# P03_Connectors.net
KiCad netlist of a schematic drawn in Altium Designer
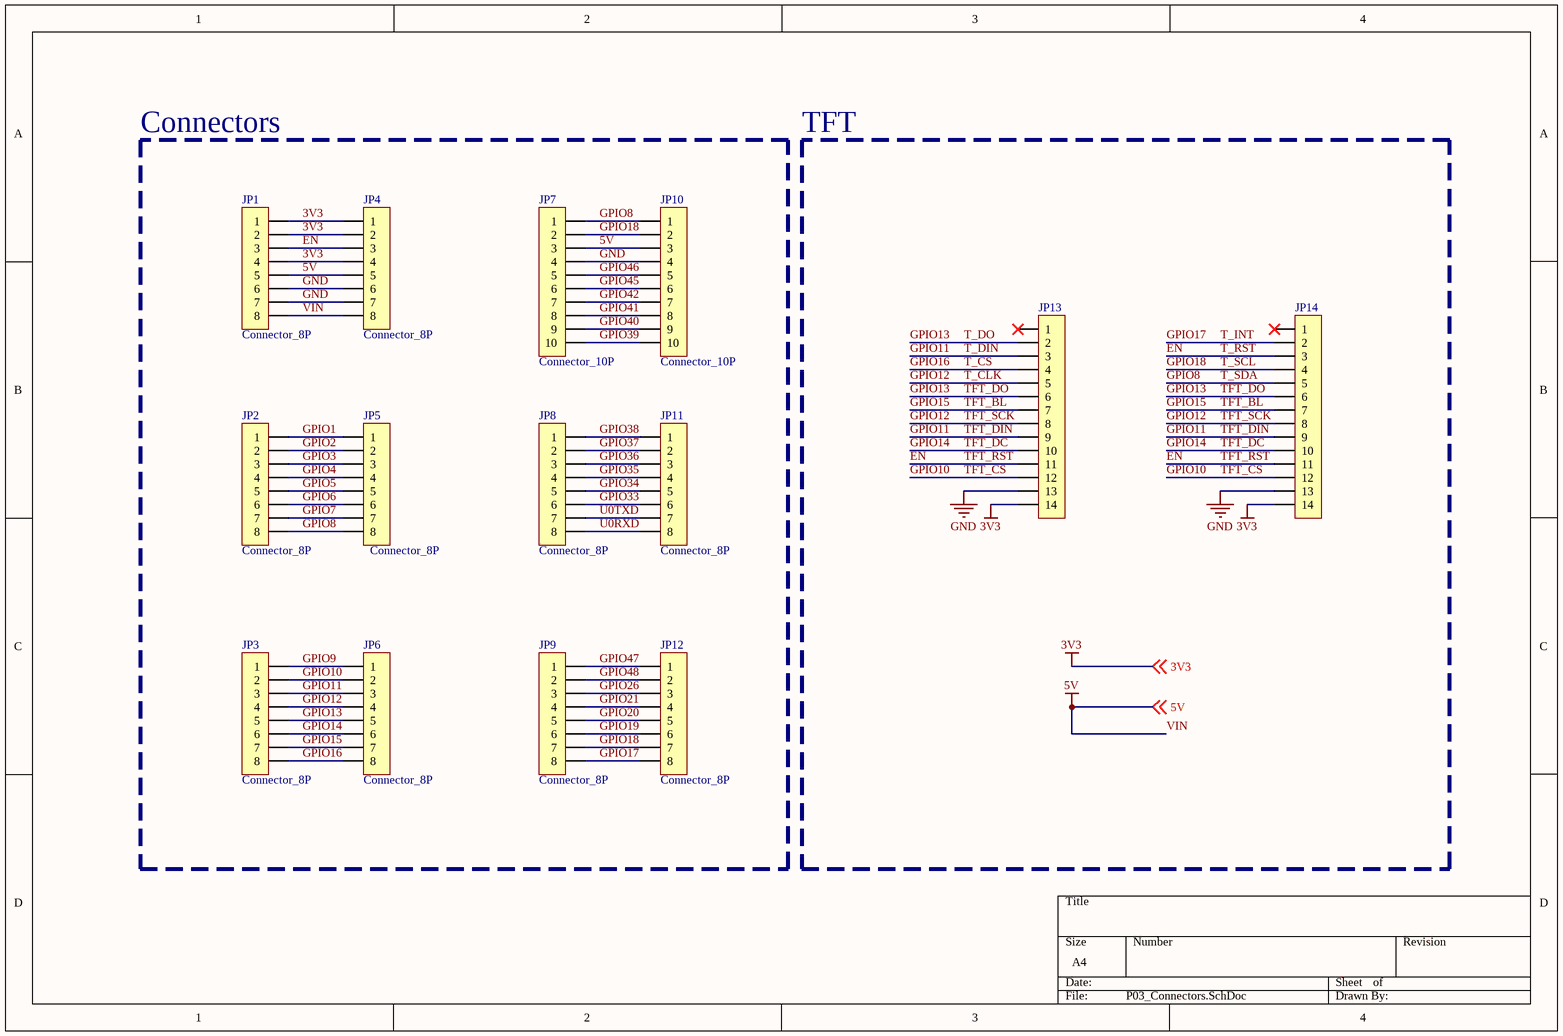
[diagram p0: P03_Connectors.SchDoc]

(export (version "E")
  (design (tool "Eeschema 10.0.6"))
  (components
    (comp (ref "JP1")
      (value "Connector_8P")
      (footprint "排母_2.54mm_8P")
      (libsource (lib "Schlib") (part "Connector_8P"))
    )
    (comp (ref "JP2")
      (value "Connector_8P")
      (footprint "排母_2.54mm_8P")
      (libsource (lib "Schlib") (part "Connector_8P"))
    )
    (comp (ref "JP3")
      (value "Connector_8P")
      (footprint "排母_2.54mm_8P")
      (libsource (lib "Schlib") (part "Connector_8P"))
    )
    (comp (ref "JP4")
      (value "Connector_8P")
      (footprint "排针_2.54mm_8P")
      (libsource (lib "") (part "Connector_8P_1"))
    )
    (comp (ref "JP5")
      (value "Connector_8P")
      (footprint "排针_2.54mm_8P")
      (libsource (lib "") (part "Connector_8P_1"))
    )
    (comp (ref "JP6")
      (value "Connector_8P")
      (footprint "排针_2.54mm_8P")
      (libsource (lib "") (part "Connector_8P_1"))
    )
    (comp (ref "JP7")
      (value "Connector_10P")
      (footprint "排母_2.54mm_10P")
      (libsource (lib "") (part "Connector_10P_1"))
    )
    (comp (ref "JP8")
      (value "Connector_8P")
      (footprint "排母_2.54mm_8P")
      (libsource (lib "Schlib") (part "Connector_8P"))
    )
    (comp (ref "JP9")
      (value "Connector_8P")
      (footprint "排母_2.54mm_8P")
      (libsource (lib "Schlib") (part "Connector_8P"))
    )
    (comp (ref "JP10")
      (value "Connector_10P")
      (footprint "排针_2.54mm_10P")
      (libsource (lib "Schlib") (part "Connector_10P"))
    )
    (comp (ref "JP11")
      (value "Connector_8P")
      (footprint "排针_2.54mm_8P")
      (libsource (lib "") (part "Connector_8P_1"))
    )
    (comp (ref "JP12")
      (value "Connector_8P")
      (footprint "排针_2.54mm_8P")
      (libsource (lib "") (part "Connector_8P_1"))
    )
    (comp (ref "JP13")
      (value "HDR-1X14")
      (footprint "HDR2.54-M-LI-14P")
      (description "14P接插件")
      (libsource (lib "5.5 - 2.54mm(100mil)连接器(XH2.54)") (part "Header 14"))
    )
    (comp (ref "JP14")
      (value "HDR-1X14")
      (footprint "HDR2.54-M-LI-14P")
      (description "14P接插件")
      (libsource (lib "5.5 - 2.54mm(100mil)连接器(XH2.54)") (part "Header 14"))
    )
  )
  (nets
    (net (code "1") (name "/EN") (class "Default")
      (node (ref "JP1") (pin "3") (pinfunction "3_3") (pintype "passive"))
      (node (ref "JP13") (pin "11") (pinfunction "11_11") (pintype "passive"))
      (node (ref "JP14") (pin "11") (pinfunction "11_11") (pintype "passive"))
      (node (ref "JP14") (pin "3") (pinfunction "3_3") (pintype "passive"))
      (node (ref "JP4") (pin "3") (pinfunction "3_3") (pintype "passive"))
    )
    (net (code "2") (name "/GPIO1") (class "Default")
      (node (ref "JP2") (pin "1") (pinfunction "1_1") (pintype "passive"))
      (node (ref "JP5") (pin "1") (pinfunction "1_1") (pintype "passive"))
    )
    (net (code "3") (name "/GPIO2") (class "Default")
      (node (ref "JP2") (pin "2") (pinfunction "2_2") (pintype "passive"))
      (node (ref "JP5") (pin "2") (pinfunction "2_2") (pintype "passive"))
    )
    (net (code "4") (name "/GPIO3") (class "Default")
      (node (ref "JP2") (pin "3") (pinfunction "3_3") (pintype "passive"))
      (node (ref "JP5") (pin "3") (pinfunction "3_3") (pintype "passive"))
    )
    (net (code "5") (name "/GPIO4") (class "Default")
      (node (ref "JP2") (pin "4") (pinfunction "4_4") (pintype "passive"))
      (node (ref "JP5") (pin "4") (pinfunction "4_4") (pintype "passive"))
    )
    (net (code "6") (name "/GPIO5") (class "Default")
      (node (ref "JP2") (pin "5") (pinfunction "5_5") (pintype "passive"))
      (node (ref "JP5") (pin "5") (pinfunction "5_5") (pintype "passive"))
    )
    (net (code "7") (name "/GPIO6") (class "Default")
      (node (ref "JP2") (pin "6") (pinfunction "6_6") (pintype "passive"))
      (node (ref "JP5") (pin "6") (pinfunction "6_6") (pintype "passive"))
    )
    (net (code "8") (name "/GPIO7") (class "Default")
      (node (ref "JP2") (pin "7") (pinfunction "7_7") (pintype "passive"))
      (node (ref "JP5") (pin "7") (pinfunction "7_7") (pintype "passive"))
    )
    (net (code "9") (name "/GPIO8") (class "Default")
      (node (ref "JP10") (pin "1") (pinfunction "1_1") (pintype "passive"))
      (node (ref "JP14") (pin "5") (pinfunction "5_5") (pintype "passive"))
      (node (ref "JP2") (pin "8") (pinfunction "8_8") (pintype "passive"))
      (node (ref "JP5") (pin "8") (pinfunction "8_8") (pintype "passive"))
      (node (ref "JP7") (pin "1") (pinfunction "1_1") (pintype "passive"))
    )
    (net (code "10") (name "/GPIO9") (class "Default")
      (node (ref "JP3") (pin "1") (pinfunction "1_1") (pintype "passive"))
      (node (ref "JP6") (pin "1") (pinfunction "1_1") (pintype "passive"))
    )
    (net (code "11") (name "/GPIO10") (class "Default")
      (node (ref "JP13") (pin "12") (pinfunction "12_12") (pintype "passive"))
      (node (ref "JP14") (pin "12") (pinfunction "12_12") (pintype "passive"))
      (node (ref "JP3") (pin "2") (pinfunction "2_2") (pintype "passive"))
      (node (ref "JP6") (pin "2") (pinfunction "2_2") (pintype "passive"))
    )
    (net (code "12") (name "/GPIO11") (class "Default")
      (node (ref "JP13") (pin "3") (pinfunction "3_3") (pintype "passive"))
      (node (ref "JP13") (pin "9") (pinfunction "9_9") (pintype "passive"))
      (node (ref "JP14") (pin "9") (pinfunction "9_9") (pintype "passive"))
      (node (ref "JP3") (pin "3") (pinfunction "3_3") (pintype "passive"))
      (node (ref "JP6") (pin "3") (pinfunction "3_3") (pintype "passive"))
    )
    (net (code "13") (name "/GPIO12") (class "Default")
      (node (ref "JP13") (pin "5") (pinfunction "5_5") (pintype "passive"))
      (node (ref "JP13") (pin "8") (pinfunction "8_8") (pintype "passive"))
      (node (ref "JP14") (pin "8") (pinfunction "8_8") (pintype "passive"))
      (node (ref "JP3") (pin "4") (pinfunction "4_4") (pintype "passive"))
      (node (ref "JP6") (pin "4") (pinfunction "4_4") (pintype "passive"))
    )
    (net (code "14") (name "/GPIO13") (class "Default")
      (node (ref "JP13") (pin "2") (pinfunction "2_2") (pintype "passive"))
      (node (ref "JP13") (pin "6") (pinfunction "6_6") (pintype "passive"))
      (node (ref "JP14") (pin "6") (pinfunction "6_6") (pintype "passive"))
      (node (ref "JP3") (pin "5") (pinfunction "5_5") (pintype "passive"))
      (node (ref "JP6") (pin "5") (pinfunction "5_5") (pintype "passive"))
    )
    (net (code "15") (name "/GPIO14") (class "Default")
      (node (ref "JP13") (pin "10") (pinfunction "10_10") (pintype "passive"))
      (node (ref "JP14") (pin "10") (pinfunction "10_10") (pintype "passive"))
      (node (ref "JP3") (pin "6") (pinfunction "6_6") (pintype "passive"))
      (node (ref "JP6") (pin "6") (pinfunction "6_6") (pintype "passive"))
    )
    (net (code "16") (name "/GPIO15") (class "Default")
      (node (ref "JP13") (pin "7") (pinfunction "7_7") (pintype "passive"))
      (node (ref "JP14") (pin "7") (pinfunction "7_7") (pintype "passive"))
      (node (ref "JP3") (pin "7") (pinfunction "7_7") (pintype "passive"))
      (node (ref "JP6") (pin "7") (pinfunction "7_7") (pintype "passive"))
    )
    (net (code "17") (name "/GPIO16") (class "Default")
      (node (ref "JP13") (pin "4") (pinfunction "4_4") (pintype "passive"))
      (node (ref "JP3") (pin "8") (pinfunction "8_8") (pintype "passive"))
      (node (ref "JP6") (pin "8") (pinfunction "8_8") (pintype "passive"))
    )
    (net (code "18") (name "/GPIO17") (class "Default")
      (node (ref "JP12") (pin "8") (pinfunction "8_8") (pintype "passive"))
      (node (ref "JP14") (pin "2") (pinfunction "2_2") (pintype "passive"))
      (node (ref "JP9") (pin "8") (pinfunction "8_8") (pintype "passive"))
    )
    (net (code "19") (name "/GPIO18") (class "Default")
      (node (ref "JP10") (pin "2") (pinfunction "2_2") (pintype "passive"))
      (node (ref "JP12") (pin "7") (pinfunction "7_7") (pintype "passive"))
      (node (ref "JP14") (pin "4") (pinfunction "4_4") (pintype "passive"))
      (node (ref "JP7") (pin "2") (pinfunction "2_2") (pintype "passive"))
      (node (ref "JP9") (pin "7") (pinfunction "7_7") (pintype "passive"))
    )
    (net (code "20") (name "/GPIO19") (class "Default")
      (node (ref "JP12") (pin "6") (pinfunction "6_6") (pintype "passive"))
      (node (ref "JP9") (pin "6") (pinfunction "6_6") (pintype "passive"))
    )
    (net (code "21") (name "/GPIO20") (class "Default")
      (node (ref "JP12") (pin "5") (pinfunction "5_5") (pintype "passive"))
      (node (ref "JP9") (pin "5") (pinfunction "5_5") (pintype "passive"))
    )
    (net (code "22") (name "/GPIO21") (class "Default")
      (node (ref "JP12") (pin "4") (pinfunction "4_4") (pintype "passive"))
      (node (ref "JP9") (pin "4") (pinfunction "4_4") (pintype "passive"))
    )
    (net (code "23") (name "/GPIO26") (class "Default")
      (node (ref "JP12") (pin "3") (pinfunction "3_3") (pintype "passive"))
      (node (ref "JP9") (pin "3") (pinfunction "3_3") (pintype "passive"))
    )
    (net (code "24") (name "/GPIO33") (class "Default")
      (node (ref "JP11") (pin "6") (pinfunction "6_6") (pintype "passive"))
      (node (ref "JP8") (pin "6") (pinfunction "6_6") (pintype "passive"))
    )
    (net (code "25") (name "/GPIO34") (class "Default")
      (node (ref "JP11") (pin "5") (pinfunction "5_5") (pintype "passive"))
      (node (ref "JP8") (pin "5") (pinfunction "5_5") (pintype "passive"))
    )
    (net (code "26") (name "/GPIO35") (class "Default")
      (node (ref "JP11") (pin "4") (pinfunction "4_4") (pintype "passive"))
      (node (ref "JP8") (pin "4") (pinfunction "4_4") (pintype "passive"))
    )
    (net (code "27") (name "/GPIO36") (class "Default")
      (node (ref "JP11") (pin "3") (pinfunction "3_3") (pintype "passive"))
      (node (ref "JP8") (pin "3") (pinfunction "3_3") (pintype "passive"))
    )
    (net (code "28") (name "/GPIO37") (class "Default")
      (node (ref "JP11") (pin "2") (pinfunction "2_2") (pintype "passive"))
      (node (ref "JP8") (pin "2") (pinfunction "2_2") (pintype "passive"))
    )
    (net (code "29") (name "/GPIO38") (class "Default")
      (node (ref "JP11") (pin "1") (pinfunction "1_1") (pintype "passive"))
      (node (ref "JP8") (pin "1") (pinfunction "1_1") (pintype "passive"))
    )
    (net (code "30") (name "/GPIO39") (class "Default")
      (node (ref "JP10") (pin "10") (pinfunction "10_10") (pintype "passive"))
      (node (ref "JP7") (pin "10") (pinfunction "10_10") (pintype "passive"))
    )
    (net (code "31") (name "/GPIO40") (class "Default")
      (node (ref "JP10") (pin "9") (pinfunction "9_9") (pintype "passive"))
      (node (ref "JP7") (pin "9") (pinfunction "9_9") (pintype "passive"))
    )
    (net (code "32") (name "/GPIO41") (class "Default")
      (node (ref "JP10") (pin "8") (pinfunction "8_8") (pintype "passive"))
      (node (ref "JP7") (pin "8") (pinfunction "8_8") (pintype "passive"))
    )
    (net (code "33") (name "/GPIO42") (class "Default")
      (node (ref "JP10") (pin "7") (pinfunction "7_7") (pintype "passive"))
      (node (ref "JP7") (pin "7") (pinfunction "7_7") (pintype "passive"))
    )
    (net (code "34") (name "/GPIO45") (class "Default")
      (node (ref "JP10") (pin "6") (pinfunction "6_6") (pintype "passive"))
      (node (ref "JP7") (pin "6") (pinfunction "6_6") (pintype "passive"))
    )
    (net (code "35") (name "/GPIO46") (class "Default")
      (node (ref "JP10") (pin "5") (pinfunction "5_5") (pintype "passive"))
      (node (ref "JP7") (pin "5") (pinfunction "5_5") (pintype "passive"))
    )
    (net (code "36") (name "/GPIO47") (class "Default")
      (node (ref "JP12") (pin "1") (pinfunction "1_1") (pintype "passive"))
      (node (ref "JP9") (pin "1") (pinfunction "1_1") (pintype "passive"))
    )
    (net (code "37") (name "/GPIO48") (class "Default")
      (node (ref "JP12") (pin "2") (pinfunction "2_2") (pintype "passive"))
      (node (ref "JP9") (pin "2") (pinfunction "2_2") (pintype "passive"))
    )
    (net (code "38") (name "/U0RXD") (class "Default")
      (node (ref "JP11") (pin "8") (pinfunction "8_8") (pintype "passive"))
      (node (ref "JP8") (pin "8") (pinfunction "8_8") (pintype "passive"))
    )
    (net (code "39") (name "/U0TXD") (class "Default")
      (node (ref "JP11") (pin "7") (pinfunction "7_7") (pintype "passive"))
      (node (ref "JP8") (pin "7") (pinfunction "7_7") (pintype "passive"))
    )
    (net (code "40") (name "3V3") (class "Default")
      (node (ref "JP1") (pin "1") (pinfunction "1_1") (pintype "passive"))
      (node (ref "JP1") (pin "2") (pinfunction "2_2") (pintype "passive"))
      (node (ref "JP1") (pin "4") (pinfunction "4_4") (pintype "passive"))
      (node (ref "JP13") (pin "14") (pinfunction "14_14") (pintype "passive"))
      (node (ref "JP14") (pin "14") (pinfunction "14_14") (pintype "passive"))
      (node (ref "JP4") (pin "1") (pinfunction "1_1") (pintype "passive"))
      (node (ref "JP4") (pin "2") (pinfunction "2_2") (pintype "passive"))
      (node (ref "JP4") (pin "4") (pinfunction "4_4") (pintype "passive"))
    )
    (net (code "41") (name "5V") (class "Default")
      (node (ref "JP1") (pin "5") (pinfunction "5_5") (pintype "passive"))
      (node (ref "JP1") (pin "8") (pinfunction "8_8") (pintype "passive"))
      (node (ref "JP10") (pin "3") (pinfunction "3_3") (pintype "passive"))
      (node (ref "JP4") (pin "5") (pinfunction "5_5") (pintype "passive"))
      (node (ref "JP4") (pin "8") (pinfunction "8_8") (pintype "passive"))
      (node (ref "JP7") (pin "3") (pinfunction "3_3") (pintype "passive"))
    )
    (net (code "42") (name "GND") (class "Default")
      (node (ref "JP1") (pin "6") (pinfunction "6_6") (pintype "passive"))
      (node (ref "JP1") (pin "7") (pinfunction "7_7") (pintype "passive"))
      (node (ref "JP10") (pin "4") (pinfunction "4_4") (pintype "passive"))
      (node (ref "JP13") (pin "13") (pinfunction "13_13") (pintype "passive"))
      (node (ref "JP14") (pin "13") (pinfunction "13_13") (pintype "passive"))
      (node (ref "JP4") (pin "6") (pinfunction "6_6") (pintype "passive"))
      (node (ref "JP4") (pin "7") (pinfunction "7_7") (pintype "passive"))
      (node (ref "JP7") (pin "4") (pinfunction "4_4") (pintype "passive"))
    )
    (net (code "43") (name "unconnected-(JP13-Pad1)") (class "Default")
      (node (ref "JP13") (pin "1") (pinfunction "1_1") (pintype "passive+no_connect"))
    )
    (net (code "44") (name "unconnected-(JP14-Pad1)") (class "Default")
      (node (ref "JP14") (pin "1") (pinfunction "1_1") (pintype "passive+no_connect"))
    )
  )
)
